# CAN_PHY.net
KiCad netlist of a schematic drawn in Altium Designer
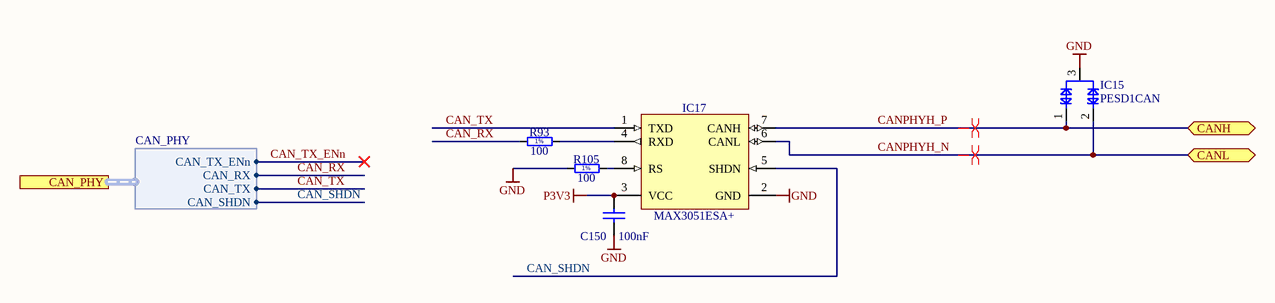
[diagram p0: CAN_PHY.SchDoc]

(export (version "E")
  (design (tool "Eeschema 10.0.6"))
  (components
    (comp (ref "C150")
      (value "100nF")
      (footprint "CAPC1005X55N")
      (description "Non-polarised capacitor")
      (fields
        (field (name "PART NUMBER") "CC0402_100NF_16V_10%_X7R")
        (field (name "VOLTAGE") "16V")
        (field (name "AUTHOR") "CERN DEM JLC")
      )
      (libsource (lib "Capacitors") (part "Capacitor - non polarized"))
    )
    (comp (ref "IC15")
      (value "PESD1CAN")
      (footprint "SOT-23")
      (description "Dual 24V ESD transient voltage suppressor")
      (libsource (lib "LIBRARY_SCH") (part "D_TVS_PESD1CAN"))
    )
    (comp (ref "IC17")
      (value "MAX3051ESA+")
      (footprint "SOIC127P600X175-8N")
      (description "+3.3V, 1Mbps, Low-Supply-Current CAN Transceiver")
      (fields (field (name "MANUFACTURER") "MAXIM") (field (name "AUTHOR") "CERN DEM JLC"))
      (libsource (lib "ICs And Semiconductors") (part "MAX3051"))
    )
    (comp (ref "R93")
      (value "100")
      (footprint "RESC1005X40N")
      (description "Resistor - 1%")
      (fields
        (field (name "PART NUMBER") "R0402_100R_1%_0.0625W_100PPM")
        (field (name "POWER") "0.0625W")
        (field (name "AUTHOR") "CERN DEM JLC")
      )
      (libsource (lib "Resistors") (part "Resistor - 1%"))
    )
    (comp (ref "R105")
      (value "100")
      (footprint "RESC1005X40N")
      (description "Resistor - 1%")
      (fields
        (field (name "PART NUMBER") "R0402_100R_1%_0.0625W_100PPM")
        (field (name "POWER") "0.0625W")
        (field (name "AUTHOR") "CERN DEM JLC")
      )
      (libsource (lib "Resistors") (part "Resistor - 1%"))
    )
  )
  (nets
    (net (code "2") (name "/CANPHYH_N") (class "Default")
      (node (ref "IC15") (pin "2") (pinfunction "2_2") (pintype "passive"))
      (node (ref "IC17") (pin "6") (pinfunction "CANL_6") (pintype "bidirectional"))
    )
    (net (code "3") (name "/CANPHYH_P") (class "Default")
      (node (ref "IC15") (pin "1") (pinfunction "1_1") (pintype "passive"))
      (node (ref "IC17") (pin "7") (pinfunction "CANH_7") (pintype "bidirectional"))
    )
    (net (code "4") (name "/CAN_RX") (class "Default")
      (node (ref "R93") (pin "1") (pinfunction "1_1") (pintype "passive"))
    )
    (net (code "5") (name "/CAN_SHDN") (class "Default")
      (node (ref "IC17") (pin "5") (pinfunction "SHDN_5") (pintype "input"))
    )
    (net (code "6") (name "/CAN_TX") (class "Default")
      (node (ref "IC17") (pin "1") (pinfunction "TXD_1") (pintype "input"))
    )
    (net (code "9") (name "GND") (class "Default")
      (node (ref "C150") (pin "1") (pinfunction "1_1") (pintype "passive"))
      (node (ref "IC15") (pin "3") (pinfunction "3_3") (pintype "passive"))
      (node (ref "IC17") (pin "2") (pinfunction "GND_2") (pintype "power_in"))
      (node (ref "R105") (pin "1") (pinfunction "1_1") (pintype "passive"))
    )
    (net (code "10") (name "Net-(IC17-RS)") (class "Default")
      (node (ref "IC17") (pin "8") (pinfunction "RS_8") (pintype "input"))
      (node (ref "R105") (pin "2") (pinfunction "2_2") (pintype "passive"))
    )
    (net (code "11") (name "Net-(IC17-RXD)") (class "Default")
      (node (ref "IC17") (pin "4") (pinfunction "RXD_4") (pintype "output"))
      (node (ref "R93") (pin "2") (pinfunction "2_2") (pintype "passive"))
    )
    (net (code "12") (name "P3V3") (class "Default")
      (node (ref "C150") (pin "2") (pinfunction "2_2") (pintype "passive"))
      (node (ref "IC17") (pin "3") (pinfunction "VCC_3") (pintype "power_in"))
    )
  )
)
